# Channel.net
KiCad netlist of a schematic drawn in Altium Designer
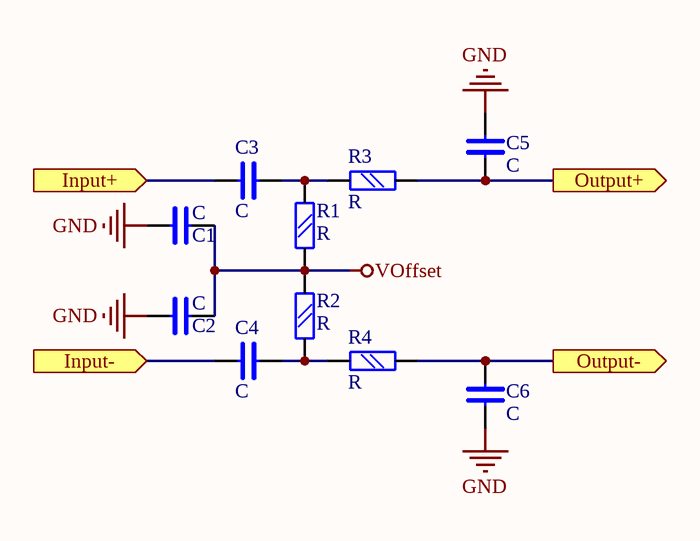
[diagram p0: Channel.SchDoc]

(export (version "E")
  (design (tool "Eeschema 10.0.6"))
  (components
    (comp (ref "C1") (value "C") (footprint "chip0603") (libsource (lib "vDevice") (part "C")))
    (comp (ref "C2") (value "C") (footprint "chip0603") (libsource (lib "vDevice") (part "C")))
    (comp (ref "C3") (value "C") (footprint "chip0603") (libsource (lib "vDevice") (part "C")))
    (comp (ref "C4") (value "C") (footprint "chip0603") (libsource (lib "vDevice") (part "C")))
    (comp (ref "C5") (value "C") (footprint "chip0603") (libsource (lib "vDevice") (part "C")))
    (comp (ref "C6") (value "C") (footprint "chip0603") (libsource (lib "vDevice") (part "C")))
    (comp (ref "R1") (value "R") (footprint "chip0603") (libsource (lib "vDevice") (part "R")))
    (comp (ref "R2") (value "R") (footprint "chip0603") (libsource (lib "vDevice") (part "R")))
    (comp (ref "R3") (value "R") (footprint "chip0603") (libsource (lib "vDevice") (part "R")))
    (comp (ref "R4") (value "R") (footprint "chip0603") (libsource (lib "vDevice") (part "R")))
  )
  (nets
    (net (code "1") (name "/Input+") (class "Default")
      (node (ref "C3") (pin "1") (pinfunction "1_1") (pintype "passive"))
    )
    (net (code "2") (name "/Input-") (class "Default")
      (node (ref "C4") (pin "1") (pinfunction "1_1") (pintype "passive"))
    )
    (net (code "3") (name "/Output+") (class "Default")
      (node (ref "C5") (pin "1") (pinfunction "1_1") (pintype "passive"))
      (node (ref "R3") (pin "2") (pinfunction "2_2") (pintype "passive"))
    )
    (net (code "4") (name "/Output-") (class "Default")
      (node (ref "C6") (pin "2") (pinfunction "2_2") (pintype "passive"))
      (node (ref "R4") (pin "2") (pinfunction "2_2") (pintype "passive"))
    )
    (net (code "5") (name "GND") (class "Default")
      (node (ref "C1") (pin "1") (pinfunction "1_1") (pintype "passive"))
      (node (ref "C2") (pin "1") (pinfunction "1_1") (pintype "passive"))
      (node (ref "C5") (pin "2") (pinfunction "2_2") (pintype "passive"))
      (node (ref "C6") (pin "1") (pinfunction "1_1") (pintype "passive"))
    )
    (net (code "6") (name "Net-(C3-Pad2)") (class "Default")
      (node (ref "C3") (pin "2") (pinfunction "2_2") (pintype "passive"))
      (node (ref "R1") (pin "2") (pinfunction "2_2") (pintype "passive"))
      (node (ref "R3") (pin "1") (pinfunction "1_1") (pintype "passive"))
    )
    (net (code "7") (name "Net-(C4-Pad2)") (class "Default")
      (node (ref "C4") (pin "2") (pinfunction "2_2") (pintype "passive"))
      (node (ref "R2") (pin "1") (pinfunction "1_1") (pintype "passive"))
      (node (ref "R4") (pin "1") (pinfunction "1_1") (pintype "passive"))
    )
    (net (code "8") (name "VOffset") (class "Default")
      (node (ref "C1") (pin "2") (pinfunction "2_2") (pintype "passive"))
      (node (ref "C2") (pin "2") (pinfunction "2_2") (pintype "passive"))
      (node (ref "R1") (pin "1") (pinfunction "1_1") (pintype "passive"))
      (node (ref "R2") (pin "2") (pinfunction "2_2") (pintype "passive"))
    )
  )
)
